# Motor1.net
KiCad netlist of a schematic drawn in Altium Designer
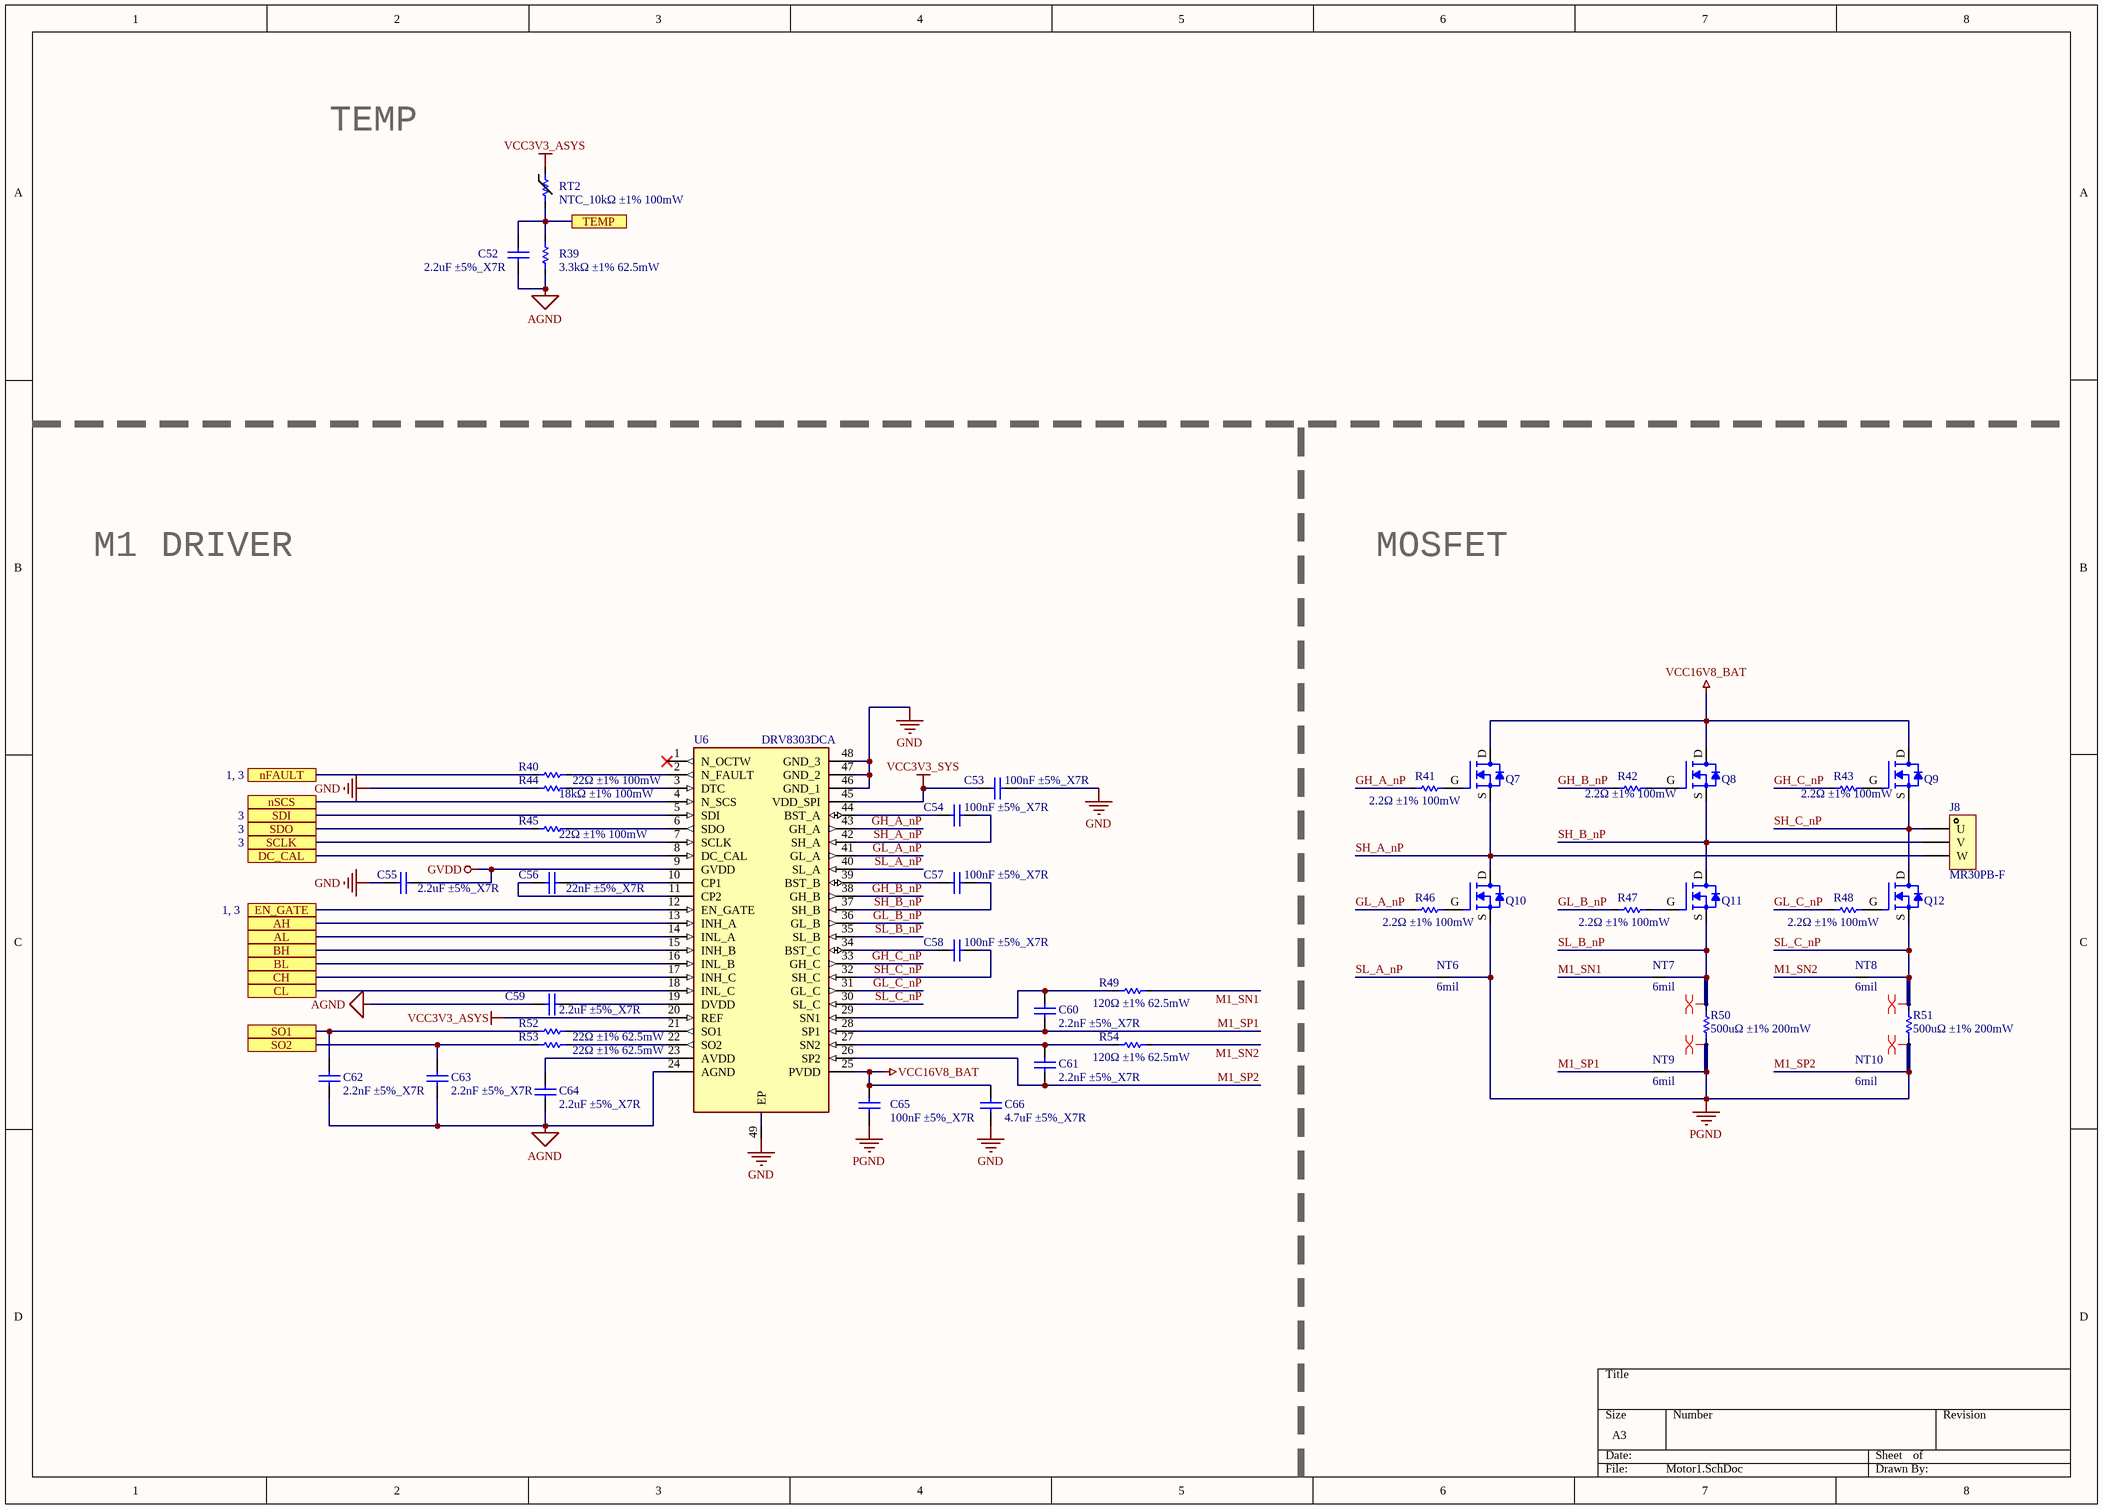
[diagram p0: Motor1.SchDoc]

(export (version "E")
  (design (tool "Eeschema 10.0.6"))
  (components
    (comp (ref "C52")
      (value "2.2uF ±5%_X7R")
      (footprint "C0402")
      (description "Capacitor")
      (fields (field (name "PUBLISHER") "Altium Limited"))
      (libsource (lib "Component") (part "Cap"))
    )
    (comp (ref "C53")
      (value "100nF ±5%_X7R")
      (footprint "C0402")
      (description "Capacitor")
      (fields (field (name "PUBLISHER") "Altium Limited"))
      (libsource (lib "Component") (part "Cap"))
    )
    (comp (ref "C54")
      (value "100nF ±5%_X7R")
      (footprint "C0402")
      (description "Capacitor")
      (fields (field (name "PUBLISHER") "Altium Limited"))
      (libsource (lib "Component") (part "Cap"))
    )
    (comp (ref "C55")
      (value "2.2uF ±5%_X7R")
      (footprint "C0402")
      (description "CL05A225KO5NQNC")
      (fields (field (name "PUBLISHER") "Altium Limited"))
      (libsource (lib "Component") (part "Cap"))
    )
    (comp (ref "C56")
      (value "22nF ±5%_X7R")
      (footprint "C0402")
      (description "Capacitor")
      (fields (field (name "PUBLISHER") "Altium Limited"))
      (libsource (lib "Component") (part "Cap"))
    )
    (comp (ref "C57")
      (value "100nF ±5%_X7R")
      (footprint "C0402")
      (description "Capacitor")
      (fields (field (name "PUBLISHER") "Altium Limited"))
      (libsource (lib "Component") (part "Cap"))
    )
    (comp (ref "C58")
      (value "100nF ±5%_X7R")
      (footprint "C0402")
      (description "Capacitor")
      (fields (field (name "PUBLISHER") "Altium Limited"))
      (libsource (lib "Component") (part "Cap"))
    )
    (comp (ref "C59")
      (value "2.2uF ±5%_X7R")
      (footprint "C0402")
      (description "CL05A225KO5NQNC")
      (fields (field (name "PUBLISHER") "Altium Limited"))
      (libsource (lib "Component") (part "Cap"))
    )
    (comp (ref "C60")
      (value "2.2nF ±5%_X7R")
      (footprint "C0402")
      (description "Capacitor")
      (fields (field (name "PUBLISHER") "Altium Limited"))
      (libsource (lib "Component") (part "Cap"))
    )
    (comp (ref "C61")
      (value "2.2nF ±5%_X7R")
      (footprint "C0402")
      (description "Capacitor")
      (fields (field (name "PUBLISHER") "Altium Limited"))
      (libsource (lib "Component") (part "Cap"))
    )
    (comp (ref "C62")
      (value "2.2nF ±5%_X7R")
      (footprint "C0402")
      (description "Capacitor")
      (fields (field (name "PUBLISHER") "Altium Limited"))
      (libsource (lib "Component") (part "Cap"))
    )
    (comp (ref "C63")
      (value "2.2nF ±5%_X7R")
      (footprint "C0402")
      (description "Capacitor")
      (fields (field (name "PUBLISHER") "Altium Limited"))
      (libsource (lib "Component") (part "Cap"))
    )
    (comp (ref "C64")
      (value "2.2uF ±5%_X7R")
      (footprint "C0402")
      (description "CL05A225KO5NQNC")
      (fields (field (name "PUBLISHER") "Altium Limited"))
      (libsource (lib "Component") (part "Cap"))
    )
    (comp (ref "C65")
      (value "100nF ±5%_X7R")
      (footprint "C0402")
      (description "Capacitor")
      (fields (field (name "PUBLISHER") "Altium Limited"))
      (libsource (lib "Component") (part "Cap"))
    )
    (comp (ref "C66")
      (value "4.7uF ±5%_X7R")
      (footprint "C0603")
      (description "Capacitor")
      (fields (field (name "PUBLISHER") "Altium Limited"))
      (libsource (lib "Component") (part "Cap"))
    )
    (comp (ref "J8")
      (value "MR30PB-F")
      (footprint "MR30PB-F [Straight] [SMT]")
      (description "驱动器端")
      (libsource (lib "Connectivity_Plugs") (part "MR30PB-F [Straight] [SMT]"))
    )
    (comp (ref "NT6") (value "6mil") (footprint "NETTIE_6mil") (libsource (lib "Component") (part "NETTIE")))
    (comp (ref "NT7") (value "6mil") (footprint "NETTIE_6mil") (libsource (lib "Component") (part "NETTIE")))
    (comp (ref "NT8") (value "6mil") (footprint "NETTIE_6mil") (libsource (lib "Component") (part "NETTIE")))
    (comp (ref "NT9") (value "6mil") (footprint "NETTIE_6mil") (libsource (lib "Component") (part "NETTIE")))
    (comp (ref "NT10") (value "6mil") (footprint "NETTIE_6mil") (libsource (lib "Component") (part "NETTIE")))
    (comp (ref "Q7")
      (value "BSC027N04LSG")
      (footprint "NRVTS10100EMFST1G")
      (description "MOSFET – Power, Single,\r\nN-Channel, PG-TDSON-8\r\nSuperSO8 5x6\r\n40 V, 139 A")
      (fields
        (field (name "MANUFACTURER") "ON Semiconductor")
        (field (name "MANUFACTURER PART NUMBER") "NTMFS4935NT1G")
      )
      (libsource (lib "Component") (part "MOSFET-N"))
    )
    (comp (ref "Q8")
      (value "BSC027N04LSG")
      (footprint "NRVTS10100EMFST1G")
      (description "MOSFET – Power, Single,\r\nN-Channel, PG-TDSON-8\r\nSuperSO8 5x6\r\n40 V, 139 A")
      (fields
        (field (name "MANUFACTURER") "ON Semiconductor")
        (field (name "MANUFACTURER PART NUMBER") "NTMFS4935NT1G")
      )
      (libsource (lib "Component") (part "MOSFET-N"))
    )
    (comp (ref "Q9")
      (value "BSC027N04LSG")
      (footprint "NRVTS10100EMFST1G")
      (description "MOSFET – Power, Single,\r\nN-Channel, PG-TDSON-8\r\nSuperSO8 5x6\r\n40 V, 139 A")
      (fields
        (field (name "MANUFACTURER") "ON Semiconductor")
        (field (name "MANUFACTURER PART NUMBER") "NTMFS4935NT1G")
      )
      (libsource (lib "Component") (part "MOSFET-N"))
    )
    (comp (ref "Q10")
      (value "BSC027N04LSG")
      (footprint "NRVTS10100EMFST1G")
      (description "MOSFET – Power, Single,\r\nN-Channel, PG-TDSON-8\r\nSuperSO8 5x6\r\n40 V, 139 A")
      (fields
        (field (name "MANUFACTURER") "ON Semiconductor")
        (field (name "MANUFACTURER PART NUMBER") "NTMFS4935NT1G")
      )
      (libsource (lib "Component") (part "MOSFET-N"))
    )
    (comp (ref "Q11")
      (value "BSC027N04LSG")
      (footprint "NRVTS10100EMFST1G")
      (description "MOSFET – Power, Single,\r\nN-Channel, PG-TDSON-8\r\nSuperSO8 5x6\r\n40 V, 139 A")
      (fields
        (field (name "MANUFACTURER") "ON Semiconductor")
        (field (name "MANUFACTURER PART NUMBER") "NTMFS4935NT1G")
      )
      (libsource (lib "Component") (part "MOSFET-N"))
    )
    (comp (ref "Q12")
      (value "BSC027N04LSG")
      (footprint "NRVTS10100EMFST1G")
      (description "MOSFET – Power, Single,\r\nN-Channel, PG-TDSON-8\r\nSuperSO8 5x6\r\n40 V, 139 A")
      (fields
        (field (name "MANUFACTURER") "ON Semiconductor")
        (field (name "MANUFACTURER PART NUMBER") "NTMFS4935NT1G")
      )
      (libsource (lib "Component") (part "MOSFET-N"))
    )
    (comp (ref "R39")
      (value "3.3kΩ ±1% 62.5mW")
      (footprint "R0402")
      (description "Resistor")
      (fields (field (name "PUBLISHER") "Altium Limited"))
      (libsource (lib "Component") (part "Res"))
    )
    (comp (ref "R40")
      (value "22Ω ±1% 100mW")
      (footprint "R0402")
      (description "Resistor")
      (fields (field (name "PUBLISHER") "Altium Limited"))
      (libsource (lib "Component") (part "Res"))
    )
    (comp (ref "R41")
      (value "2.2Ω ±1% 100mW")
      (footprint "R0402")
      (description "Resistor")
      (fields (field (name "PUBLISHER") "Altium Limited"))
      (libsource (lib "Component") (part "Res"))
    )
    (comp (ref "R42")
      (value "2.2Ω ±1% 100mW")
      (footprint "R0402")
      (description "Resistor")
      (fields (field (name "PUBLISHER") "Altium Limited"))
      (libsource (lib "Component") (part "Res"))
    )
    (comp (ref "R43")
      (value "2.2Ω ±1% 100mW")
      (footprint "R0402")
      (description "Resistor")
      (fields (field (name "PUBLISHER") "Altium Limited"))
      (libsource (lib "Component") (part "Res"))
    )
    (comp (ref "R44")
      (value "18kΩ ±1% 100mW")
      (footprint "R0402")
      (description "Resistor")
      (fields (field (name "PUBLISHER") "Altium Limited"))
      (libsource (lib "Component") (part "Res"))
    )
    (comp (ref "R45")
      (value "22Ω ±1% 100mW")
      (footprint "R0402")
      (description "Resistor")
      (fields (field (name "PUBLISHER") "Altium Limited"))
      (libsource (lib "Component") (part "Res"))
    )
    (comp (ref "R46")
      (value "2.2Ω ±1% 100mW")
      (footprint "R0402")
      (description "Resistor")
      (fields (field (name "PUBLISHER") "Altium Limited"))
      (libsource (lib "Component") (part "Res"))
    )
    (comp (ref "R47")
      (value "2.2Ω ±1% 100mW")
      (footprint "R0402")
      (description "Resistor")
      (fields (field (name "PUBLISHER") "Altium Limited"))
      (libsource (lib "Component") (part "Res"))
    )
    (comp (ref "R48")
      (value "2.2Ω ±1% 100mW")
      (footprint "R0402")
      (description "Resistor")
      (fields (field (name "PUBLISHER") "Altium Limited"))
      (libsource (lib "Component") (part "Res"))
    )
    (comp (ref "R49")
      (value "120Ω ±1% 62.5mW")
      (footprint "R0402")
      (description "Resistor")
      (fields (field (name "PUBLISHER") "Altium Limited"))
      (libsource (lib "Component") (part "Res"))
    )
    (comp (ref "R50")
      (value "500uΩ ±1% 200mW")
      (footprint "R2512")
      (description "Resistor")
      (fields (field (name "PUBLISHER") "Altium Limited"))
      (libsource (lib "Component") (part "Res"))
    )
    (comp (ref "R51")
      (value "500uΩ ±1% 200mW")
      (footprint "R2512")
      (description "Resistor")
      (fields (field (name "PUBLISHER") "Altium Limited"))
      (libsource (lib "Component") (part "Res"))
    )
    (comp (ref "R52")
      (value "22Ω ±1% 62.5mW")
      (footprint "R0402")
      (description "Resistor")
      (fields (field (name "PUBLISHER") "Altium Limited"))
      (libsource (lib "Component") (part "Res"))
    )
    (comp (ref "R53")
      (value "22Ω ±1% 62.5mW")
      (footprint "R0402")
      (description "Resistor")
      (fields (field (name "PUBLISHER") "Altium Limited"))
      (libsource (lib "Component") (part "Res"))
    )
    (comp (ref "R54")
      (value "120Ω ±1% 62.5mW")
      (footprint "R0402")
      (description "Resistor")
      (fields (field (name "PUBLISHER") "Altium Limited"))
      (libsource (lib "Component") (part "Res"))
    )
    (comp (ref "RT2")
      (value "NTC_10kΩ ±1% 100mW")
      (footprint "R0402")
      (description "THERMISTOR 10K OHM NTC 0402 SMD")
      (libsource (lib "Component") (part "TEMP RES"))
    )
    (comp (ref "U6")
      (value "DRV8303DCA")
      (footprint "SamacSys:SOP50P810X120-49N")
      (description "Integrated Circuit")
      (fields (field (name "MOUSER PART NUMBER") "595-DRV8303DCA"))
      (libsource (lib "*") (part "DRV8303DCA"))
    )
  )
  (nets
    (net (code "1") (name "/AH") (class "Default")
      (node (ref "U6") (pin "13") (pinfunction "INH_A_13") (pintype "input"))
    )
    (net (code "2") (name "/AL") (class "Default")
      (node (ref "U6") (pin "14") (pinfunction "INL_A_14") (pintype "input"))
    )
    (net (code "3") (name "/BH") (class "Default")
      (node (ref "U6") (pin "15") (pinfunction "INH_B_15") (pintype "input"))
    )
    (net (code "4") (name "/BL") (class "Default")
      (node (ref "U6") (pin "16") (pinfunction "INL_B_16") (pintype "input"))
    )
    (net (code "5") (name "/CH") (class "Default")
      (node (ref "U6") (pin "17") (pinfunction "INH_C_17") (pintype "input"))
    )
    (net (code "6") (name "/CL") (class "Default")
      (node (ref "U6") (pin "18") (pinfunction "INL_C_18") (pintype "input"))
    )
    (net (code "7") (name "/DC_CAL") (class "Default")
      (node (ref "U6") (pin "8") (pinfunction "DC_CAL_8") (pintype "input"))
    )
    (net (code "8") (name "/EN_GATE") (class "Default")
      (node (ref "U6") (pin "12") (pinfunction "EN_GATE_12") (pintype "input"))
    )
    (net (code "9") (name "/GH_A_nP") (class "Default")
      (node (ref "R41") (pin "2") (pinfunction "2_2") (pintype "passive"))
      (node (ref "U6") (pin "43") (pinfunction "GH_A_43") (pintype "output"))
    )
    (net (code "10") (name "/GH_B_nP") (class "Default")
      (node (ref "R42") (pin "2") (pinfunction "2_2") (pintype "passive"))
      (node (ref "U6") (pin "38") (pinfunction "GH_B_38") (pintype "output"))
    )
    (net (code "11") (name "/GH_C_nP") (class "Default")
      (node (ref "R43") (pin "2") (pinfunction "2_2") (pintype "passive"))
      (node (ref "U6") (pin "33") (pinfunction "GH_C_33") (pintype "output"))
    )
    (net (code "12") (name "/GL_A_nP") (class "Default")
      (node (ref "R46") (pin "2") (pinfunction "2_2") (pintype "passive"))
      (node (ref "U6") (pin "41") (pinfunction "GL_A_41") (pintype "output"))
    )
    (net (code "13") (name "/GL_B_nP") (class "Default")
      (node (ref "R47") (pin "2") (pinfunction "2_2") (pintype "passive"))
      (node (ref "U6") (pin "36") (pinfunction "GL_B_36") (pintype "output"))
    )
    (net (code "14") (name "/GL_C_nP") (class "Default")
      (node (ref "R48") (pin "2") (pinfunction "2_2") (pintype "passive"))
      (node (ref "U6") (pin "31") (pinfunction "GL_C_31") (pintype "output"))
    )
    (net (code "15") (name "/M1_SN1") (class "Default")
      (node (ref "NT7") (pin "1") (pinfunction "1_1") (pintype "passive"))
      (node (ref "R49") (pin "1") (pinfunction "1_1") (pintype "passive"))
    )
    (net (code "16") (name "/M1_SN2") (class "Default")
      (node (ref "NT8") (pin "1") (pinfunction "1_1") (pintype "passive"))
      (node (ref "R54") (pin "1") (pinfunction "1_1") (pintype "passive"))
    )
    (net (code "17") (name "/M1_SP1") (class "Default")
      (node (ref "C60") (pin "1") (pinfunction "1_1") (pintype "passive"))
      (node (ref "NT9") (pin "1") (pinfunction "1_1") (pintype "passive"))
      (node (ref "U6") (pin "28") (pinfunction "SP1_28") (pintype "input"))
    )
    (net (code "18") (name "/M1_SP2") (class "Default")
      (node (ref "C61") (pin "1") (pinfunction "1_1") (pintype "passive"))
      (node (ref "NT10") (pin "1") (pinfunction "1_1") (pintype "passive"))
      (node (ref "U6") (pin "26") (pinfunction "SP2_26") (pintype "input"))
    )
    (net (code "19") (name "/SCLK") (class "Default")
      (node (ref "U6") (pin "7") (pinfunction "SCLK_7") (pintype "input"))
    )
    (net (code "20") (name "/SDI") (class "Default")
      (node (ref "U6") (pin "5") (pinfunction "SDI_5") (pintype "input"))
    )
    (net (code "21") (name "/SDO") (class "Default")
      (node (ref "R45") (pin "1") (pinfunction "1_1") (pintype "passive"))
    )
    (net (code "22") (name "/SH_A_nP") (class "Default")
      (node (ref "C54") (pin "1") (pinfunction "1_1") (pintype "passive"))
      (node (ref "J8") (pin "3") (pinfunction "W_3") (pintype "passive"))
      (node (ref "Q10") (pin "D") (pinfunction "D_D") (pintype "passive"))
      (node (ref "Q7") (pin "S") (pinfunction "S_S") (pintype "passive"))
      (node (ref "U6") (pin "42") (pinfunction "SH_A_42") (pintype "input"))
    )
    (net (code "23") (name "/SH_B_nP") (class "Default")
      (node (ref "C57") (pin "1") (pinfunction "1_1") (pintype "passive"))
      (node (ref "J8") (pin "2") (pinfunction "V_2") (pintype "passive"))
      (node (ref "Q11") (pin "D") (pinfunction "D_D") (pintype "passive"))
      (node (ref "Q8") (pin "S") (pinfunction "S_S") (pintype "passive"))
      (node (ref "U6") (pin "37") (pinfunction "SH_B_37") (pintype "input"))
    )
    (net (code "24") (name "/SH_C_nP") (class "Default")
      (node (ref "C58") (pin "1") (pinfunction "1_1") (pintype "passive"))
      (node (ref "J8") (pin "1") (pinfunction "U_1") (pintype "passive"))
      (node (ref "Q12") (pin "D") (pinfunction "D_D") (pintype "passive"))
      (node (ref "Q9") (pin "S") (pinfunction "S_S") (pintype "passive"))
      (node (ref "U6") (pin "32") (pinfunction "SH_C_32") (pintype "input"))
    )
    (net (code "25") (name "/SL_A_nP") (class "Default")
      (node (ref "NT6") (pin "2") (pinfunction "2_2") (pintype "passive"))
      (node (ref "U6") (pin "40") (pinfunction "SL_A_40") (pintype "input"))
    )
    (net (code "26") (name "/SL_B_nP") (class "Default")
      (node (ref "NT7") (pin "2") (pinfunction "2_2") (pintype "passive"))
      (node (ref "Q11") (pin "S") (pinfunction "S_S") (pintype "passive"))
      (node (ref "R50") (pin "2") (pinfunction "2_2") (pintype "passive"))
      (node (ref "U6") (pin "35") (pinfunction "SL_B_35") (pintype "input"))
    )
    (net (code "27") (name "/SL_C_nP") (class "Default")
      (node (ref "NT8") (pin "2") (pinfunction "2_2") (pintype "passive"))
      (node (ref "Q12") (pin "S") (pinfunction "S_S") (pintype "passive"))
      (node (ref "R51") (pin "2") (pinfunction "2_2") (pintype "passive"))
      (node (ref "U6") (pin "30") (pinfunction "SL_C_30") (pintype "input"))
    )
    (net (code "28") (name "/SO1") (class "Default")
      (node (ref "C62") (pin "2") (pinfunction "2_2") (pintype "passive"))
      (node (ref "R52") (pin "2") (pinfunction "2_2") (pintype "passive"))
    )
    (net (code "29") (name "/SO2") (class "Default")
      (node (ref "C63") (pin "2") (pinfunction "2_2") (pintype "passive"))
      (node (ref "R53") (pin "2") (pinfunction "2_2") (pintype "passive"))
    )
    (net (code "30") (name "/TEMP") (class "Default")
      (node (ref "C52") (pin "2") (pinfunction "2_2") (pintype "passive"))
      (node (ref "R39") (pin "2") (pinfunction "2_2") (pintype "passive"))
      (node (ref "RT2") (pin "2") (pinfunction "2_2") (pintype "passive"))
    )
    (net (code "31") (name "/nFAULT") (class "Default")
      (node (ref "R40") (pin "1") (pinfunction "1_1") (pintype "passive"))
    )
    (net (code "32") (name "/nSCS") (class "Default")
      (node (ref "U6") (pin "4") (pinfunction "N_SCS_4") (pintype "input"))
    )
    (net (code "33") (name "AGND") (class "Default")
      (node (ref "C52") (pin "1") (pinfunction "1_1") (pintype "passive"))
      (node (ref "C59") (pin "2") (pinfunction "2_2") (pintype "passive"))
      (node (ref "C62") (pin "1") (pinfunction "1_1") (pintype "passive"))
      (node (ref "C63") (pin "1") (pinfunction "1_1") (pintype "passive"))
      (node (ref "C64") (pin "1") (pinfunction "1_1") (pintype "passive"))
      (node (ref "R39") (pin "1") (pinfunction "1_1") (pintype "passive"))
      (node (ref "U6") (pin "24") (pinfunction "AGND_24") (pintype "power_in"))
    )
    (net (code "34") (name "GND") (class "Default")
      (node (ref "C53") (pin "1") (pinfunction "1_1") (pintype "passive"))
      (node (ref "C55") (pin "1") (pinfunction "1_1") (pintype "passive"))
      (node (ref "C66") (pin "1") (pinfunction "1_1") (pintype "passive"))
      (node (ref "R44") (pin "2") (pinfunction "2_2") (pintype "passive"))
      (node (ref "U6") (pin "46") (pinfunction "GND_1_46") (pintype "power_in"))
      (node (ref "U6") (pin "47") (pinfunction "GND_2_47") (pintype "power_in"))
      (node (ref "U6") (pin "48") (pinfunction "GND_3_48") (pintype "power_in"))
      (node (ref "U6") (pin "49") (pinfunction "EP_49") (pintype "passive"))
    )
    (net (code "35") (name "GVDD") (class "Default")
      (node (ref "C55") (pin "2") (pinfunction "2_2") (pintype "passive"))
      (node (ref "U6") (pin "9") (pinfunction "GVDD_9") (pintype "power_in"))
    )
    (net (code "36") (name "Net-(Q7-PadG)") (class "Default")
      (node (ref "Q7") (pin "G") (pinfunction "G_G") (pintype "passive"))
      (node (ref "R41") (pin "1") (pinfunction "1_1") (pintype "passive"))
    )
    (net (code "37") (name "Net-(Q8-PadG)") (class "Default")
      (node (ref "Q8") (pin "G") (pinfunction "G_G") (pintype "passive"))
      (node (ref "R42") (pin "1") (pinfunction "1_1") (pintype "passive"))
    )
    (net (code "38") (name "Net-(Q9-PadG)") (class "Default")
      (node (ref "Q9") (pin "G") (pinfunction "G_G") (pintype "passive"))
      (node (ref "R43") (pin "1") (pinfunction "1_1") (pintype "passive"))
    )
    (net (code "39") (name "Net-(Q10-PadG)") (class "Default")
      (node (ref "Q10") (pin "G") (pinfunction "G_G") (pintype "passive"))
      (node (ref "R46") (pin "1") (pinfunction "1_1") (pintype "passive"))
    )
    (net (code "40") (name "Net-(Q11-PadG)") (class "Default")
      (node (ref "Q11") (pin "G") (pinfunction "G_G") (pintype "passive"))
      (node (ref "R47") (pin "1") (pinfunction "1_1") (pintype "passive"))
    )
    (net (code "41") (name "Net-(Q12-PadG)") (class "Default")
      (node (ref "Q12") (pin "G") (pinfunction "G_G") (pintype "passive"))
      (node (ref "R48") (pin "1") (pinfunction "1_1") (pintype "passive"))
    )
    (net (code "42") (name "Net-(U6-AVDD)") (class "Default")
      (node (ref "C64") (pin "2") (pinfunction "2_2") (pintype "passive"))
      (node (ref "U6") (pin "23") (pinfunction "AVDD_23") (pintype "power_in"))
    )
    (net (code "43") (name "Net-(U6-BST_A)") (class "Default")
      (node (ref "C54") (pin "2") (pinfunction "2_2") (pintype "passive"))
      (node (ref "U6") (pin "44") (pinfunction "BST_A_44") (pintype "bidirectional"))
    )
    (net (code "44") (name "Net-(U6-BST_B)") (class "Default")
      (node (ref "C57") (pin "2") (pinfunction "2_2") (pintype "passive"))
      (node (ref "U6") (pin "39") (pinfunction "BST_B_39") (pintype "bidirectional"))
    )
    (net (code "45") (name "Net-(U6-BST_C)") (class "Default")
      (node (ref "C58") (pin "2") (pinfunction "2_2") (pintype "passive"))
      (node (ref "U6") (pin "34") (pinfunction "BST_C_34") (pintype "bidirectional"))
    )
    (net (code "46") (name "Net-(U6-CP1)") (class "Default")
      (node (ref "C56") (pin "1") (pinfunction "1_1") (pintype "passive"))
      (node (ref "U6") (pin "10") (pinfunction "CP1_10") (pintype "power_in"))
    )
    (net (code "47") (name "Net-(U6-CP2)") (class "Default")
      (node (ref "C56") (pin "2") (pinfunction "2_2") (pintype "passive"))
      (node (ref "U6") (pin "11") (pinfunction "CP2_11") (pintype "power_in"))
    )
    (net (code "48") (name "Net-(U6-DTC)") (class "Default")
      (node (ref "R44") (pin "1") (pinfunction "1_1") (pintype "passive"))
      (node (ref "U6") (pin "3") (pinfunction "DTC_3") (pintype "input"))
    )
    (net (code "49") (name "Net-(U6-DVDD)") (class "Default")
      (node (ref "C59") (pin "1") (pinfunction "1_1") (pintype "passive"))
      (node (ref "U6") (pin "19") (pinfunction "DVDD_19") (pintype "power_in"))
    )
    (net (code "50") (name "Net-(U6-N_FAULT)") (class "Default")
      (node (ref "R40") (pin "2") (pinfunction "2_2") (pintype "passive"))
      (node (ref "U6") (pin "2") (pinfunction "N_FAULT_2") (pintype "output"))
    )
    (net (code "51") (name "Net-(U6-SDO)") (class "Default")
      (node (ref "R45") (pin "2") (pinfunction "2_2") (pintype "passive"))
      (node (ref "U6") (pin "6") (pinfunction "SDO_6") (pintype "output"))
    )
    (net (code "52") (name "Net-(U6-SN1)") (class "Default")
      (node (ref "C60") (pin "2") (pinfunction "2_2") (pintype "passive"))
      (node (ref "R49") (pin "2") (pinfunction "2_2") (pintype "passive"))
      (node (ref "U6") (pin "29") (pinfunction "SN1_29") (pintype "input"))
    )
    (net (code "53") (name "Net-(U6-SN2)") (class "Default")
      (node (ref "C61") (pin "2") (pinfunction "2_2") (pintype "passive"))
      (node (ref "R54") (pin "2") (pinfunction "2_2") (pintype "passive"))
      (node (ref "U6") (pin "27") (pinfunction "SN2_27") (pintype "input"))
    )
    (net (code "54") (name "Net-(U6-SO1)") (class "Default")
      (node (ref "R52") (pin "1") (pinfunction "1_1") (pintype "passive"))
      (node (ref "U6") (pin "21") (pinfunction "SO1_21") (pintype "output"))
    )
    (net (code "55") (name "Net-(U6-SO2)") (class "Default")
      (node (ref "R53") (pin "1") (pinfunction "1_1") (pintype "passive"))
      (node (ref "U6") (pin "22") (pinfunction "SO2_22") (pintype "output"))
    )
    (net (code "56") (name "PGND") (class "Default")
      (node (ref "C65") (pin "1") (pinfunction "1_1") (pintype "passive"))
      (node (ref "NT10") (pin "2") (pinfunction "2_2") (pintype "passive"))
      (node (ref "NT6") (pin "1") (pinfunction "1_1") (pintype "passive"))
      (node (ref "NT9") (pin "2") (pinfunction "2_2") (pintype "passive"))
      (node (ref "Q10") (pin "S") (pinfunction "S_S") (pintype "passive"))
      (node (ref "R50") (pin "1") (pinfunction "1_1") (pintype "passive"))
      (node (ref "R51") (pin "1") (pinfunction "1_1") (pintype "passive"))
    )
    (net (code "57") (name "VCC3V3_ASYS") (class "Default")
      (node (ref "RT2") (pin "1") (pinfunction "1_1") (pintype "passive"))
      (node (ref "U6") (pin "20") (pinfunction "REF_20") (pintype "input"))
    )
    (net (code "58") (name "VCC3V3_SYS") (class "Default")
      (node (ref "C53") (pin "2") (pinfunction "2_2") (pintype "passive"))
      (node (ref "U6") (pin "45") (pinfunction "VDD_SPI_45") (pintype "power_in"))
    )
    (net (code "59") (name "VCC16V8_BAT") (class "Default")
      (node (ref "C65") (pin "2") (pinfunction "2_2") (pintype "passive"))
      (node (ref "C66") (pin "2") (pinfunction "2_2") (pintype "passive"))
      (node (ref "Q7") (pin "D") (pinfunction "D_D") (pintype "passive"))
      (node (ref "Q8") (pin "D") (pinfunction "D_D") (pintype "passive"))
      (node (ref "Q9") (pin "D") (pinfunction "D_D") (pintype "passive"))
      (node (ref "U6") (pin "25") (pinfunction "PVDD_25") (pintype "power_in"))
    )
    (net (code "60") (name "unconnected-(U6-N_OCTW-Pad1)") (class "Default")
      (node (ref "U6") (pin "1") (pinfunction "N_OCTW_1") (pintype "output+no_connect"))
    )
  )
)
